# RNG_Board.net
KiCad netlist of a schematic drawn in EAGLE
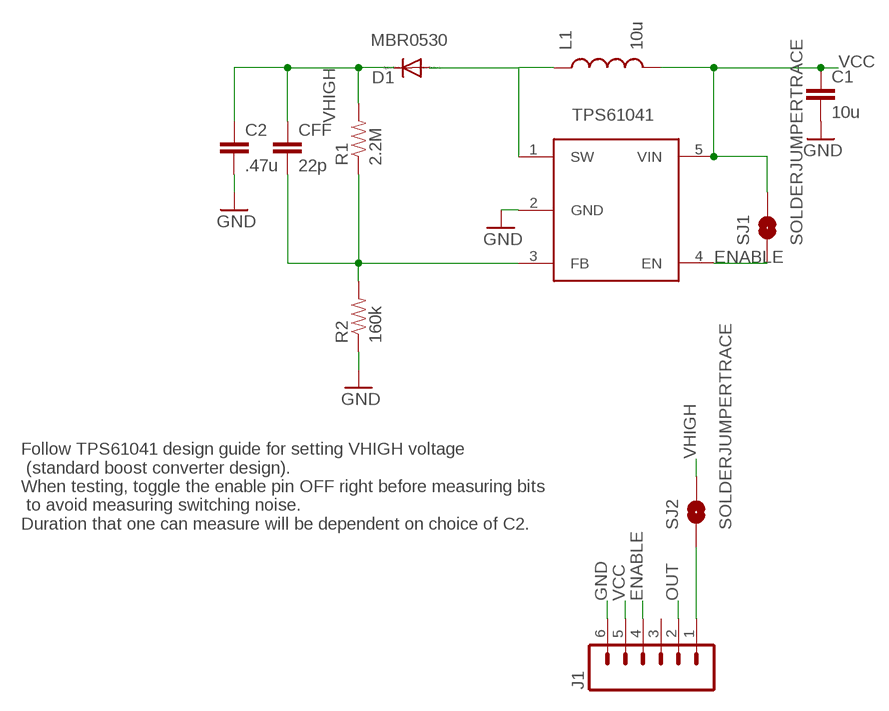
[diagram p0: schematic, sheet 1]
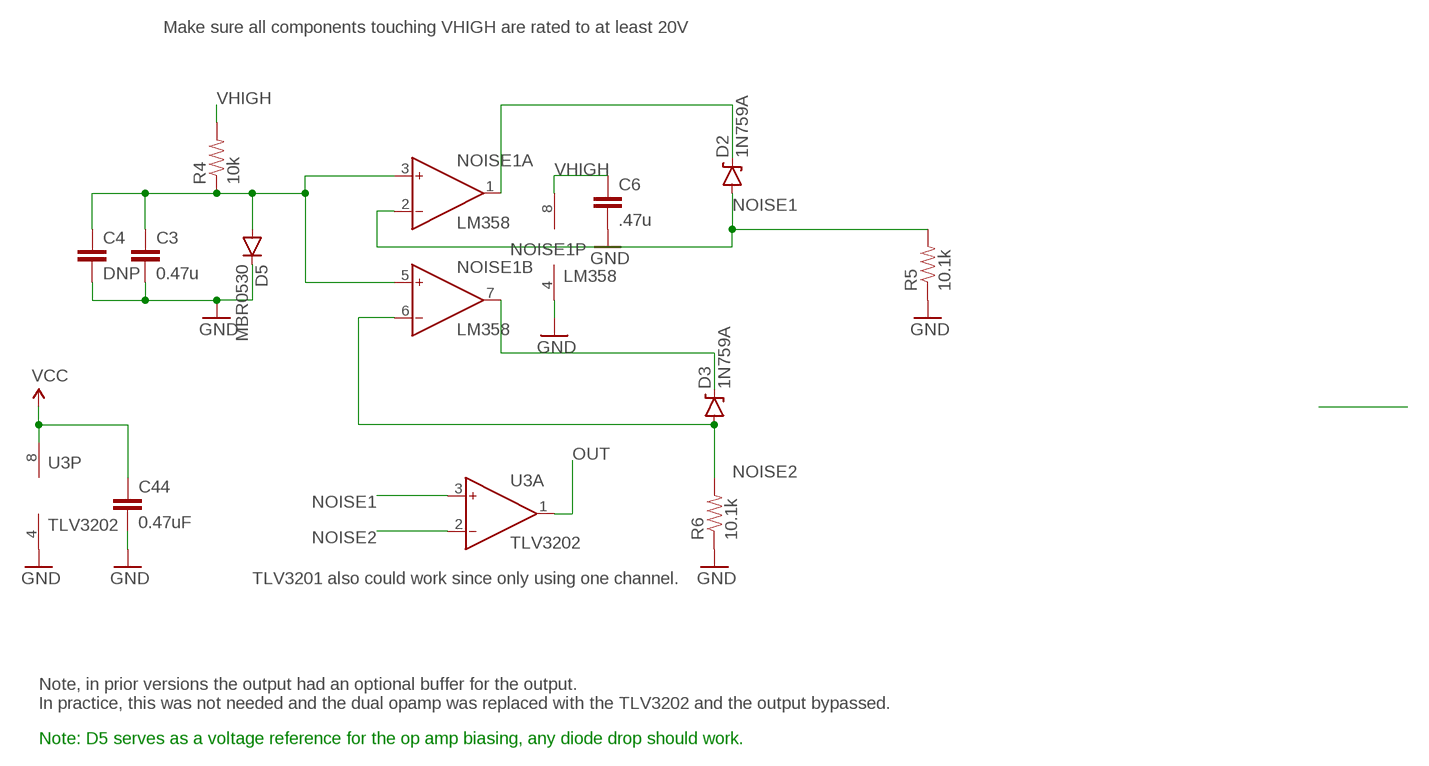
[diagram p1: schematic, sheet 2]

(export (version "E")
  (design (tool "Eeschema 10.0.6"))
  (components
    (comp (ref "C1")
      (value "10u")
      (footprint "eagle-import:0603-CAP")
      (libsource (lib "eagle-import") (part "CAP0603-CAP"))
    )
    (comp (ref "C2")
      (value ".47u")
      (footprint "eagle-import:0603-CAP")
      (libsource (lib "eagle-import") (part "CAP0603-CAP"))
    )
    (comp (ref "CFF")
      (value "22p")
      (footprint "eagle-import:0603-CAP")
      (libsource (lib "eagle-import") (part "CAP0603-CAP"))
    )
    (comp (ref "D1")
      (value "MBR0530")
      (footprint "eagle-import:SOD-123_MINI-SMA")
      (libsource (lib "eagle-import") (part "CGRM400-G1"))
    )
    (comp (ref "J1")
      (value "M06SILK_FEMALE_PTH")
      (footprint "eagle-import:1X06")
      (libsource (lib "eagle-import") (part "M06SILK_FEMALE_PTH"))
    )
    (comp (ref "L1")
      (value "10u")
      (footprint "eagle-import:0805")
      (libsource (lib "eagle-import") (part "INDUCTOR0805"))
    )
    (comp (ref "R1")
      (value "2.2M")
      (footprint "eagle-import:0603-RES")
      (libsource (lib "eagle-import") (part "0.27OHM-1/10W-1%(0603)"))
    )
    (comp (ref "R2")
      (value "160k")
      (footprint "eagle-import:0603-RES")
      (libsource (lib "eagle-import") (part "0.27OHM-1/10W-1%(0603)"))
    )
    (comp (ref "SJ1")
      (value "SOLDERJUMPERTRACE")
      (footprint "eagle-import:SJ_2S-TRACE")
      (libsource (lib "eagle-import") (part "SOLDERJUMPERTRACE"))
    )
    (comp (ref "SJ2")
      (value "SOLDERJUMPERTRACE")
      (footprint "eagle-import:SJ_2S-TRACE")
      (libsource (lib "eagle-import") (part "SOLDERJUMPERTRACE"))
    )
    (comp (ref "U$1")
      (value "TPS61040")
      (footprint "eagle-import:SOT23-5")
      (libsource (lib "eagle-import") (part "TPS61040"))
    )
    (comp (ref "C3")
      (value "0.47u")
      (footprint "eagle-import:0603-CAP")
      (libsource (lib "eagle-import") (part "SparkFun-Passives_CAP0603-CAP"))
    )
    (comp (ref "C4")
      (value "DNP")
      (footprint "eagle-import:0603-CAP")
      (libsource (lib "eagle-import") (part "SparkFun-Passives_CAP0603-CAP"))
    )
    (comp (ref "C6")
      (value ".47u")
      (footprint "eagle-import:0603-CAP")
      (libsource (lib "eagle-import") (part "CAP0603-CAP"))
    )
    (comp (ref "C44")
      (value "0.47uF")
      (footprint "eagle-import:C0603")
      (libsource (lib "eagle-import") (part "C-EUC0603"))
    )
    (comp (ref "D2")
      (value "1N759A")
      (footprint "eagle-import:DIODE-ZENER")
      (fields (field (name "MPN") "610-1N759A"))
      (libsource (lib "eagle-import") (part "DIODE-ZENERPTH"))
    )
    (comp (ref "D3")
      (value "1N759A")
      (footprint "eagle-import:DIODE-ZENER")
      (fields (field (name "MPN") "610-1N759A"))
      (libsource (lib "eagle-import") (part "DIODE-ZENERPTH"))
    )
    (comp (ref "D5")
      (value "MBR0530")
      (footprint "eagle-import:SOD-123")
      (libsource (lib "eagle-import") (part "DIODESOD123"))
    )
    (comp (ref "NOISE1")
      (value "LM358")
      (footprint "eagle-import:SO8")
      (fields (field (name "MF") "ALTERA CORPORATION") (field (name "MPN") "AD712KRZ"))
      (libsource (lib "eagle-import") (part "AD712R"))
    )
    (comp (ref "R4")
      (value "10k")
      (footprint "eagle-import:0603-RES")
      (libsource (lib "eagle-import") (part "RESISTOR0603"))
    )
    (comp (ref "R5")
      (value "10.1k")
      (footprint "eagle-import:0603-RES")
      (libsource (lib "eagle-import") (part "RESISTOR0603"))
    )
    (comp (ref "R6")
      (value "10.1k")
      (footprint "eagle-import:0603-RES")
      (libsource (lib "eagle-import") (part "RESISTOR0603"))
    )
    (comp (ref "U3")
      (value "TLV3202")
      (footprint "eagle-import:SO8")
      (fields
        (field (name "MF") "ALTERA CORPORATION")
        (field (name "MPN") "AD712KRZ")
        (field (name "DKPN") "296-34773-1-ND")
      )
      (libsource (lib "eagle-import") (part "imix_AD712R"))
    )
  )
  (nets
    (net (code "1") (name "ENABLE") (class "Default")
      (node (ref "J1") (pin "4") (pinfunction "4_4") (pintype "passive"))
      (node (ref "SJ1") (pin "1") (pinfunction "1_1") (pintype "passive"))
      (node (ref "U$1") (pin "4") (pinfunction "EN_4") (pintype "bidirectional"))
    )
    (net (code "2") (name "GND") (class "Default")
      (node (ref "C1") (pin "2") (pinfunction "2_2") (pintype "passive"))
      (node (ref "C2") (pin "2") (pinfunction "2_2") (pintype "passive"))
      (node (ref "C3") (pin "2") (pinfunction "2_2") (pintype "passive"))
      (node (ref "C4") (pin "2") (pinfunction "2_2") (pintype "passive"))
      (node (ref "C44") (pin "2") (pinfunction "2_2") (pintype "passive"))
      (node (ref "C6") (pin "2") (pinfunction "2_2") (pintype "passive"))
      (node (ref "D5") (pin "C") (pinfunction "C_C") (pintype "passive"))
      (node (ref "J1") (pin "6") (pinfunction "6_6") (pintype "passive"))
      (node (ref "NOISE1") (pin "4") (pinfunction "V-_4") (pintype "power_in"))
      (node (ref "R2") (pin "1") (pinfunction "1_1") (pintype "passive"))
      (node (ref "R5") (pin "1") (pinfunction "1_1") (pintype "passive"))
      (node (ref "R6") (pin "1") (pinfunction "1_1") (pintype "passive"))
      (node (ref "U$1") (pin "2") (pinfunction "GND_2") (pintype "bidirectional"))
      (node (ref "U3") (pin "4") (pinfunction "V-_4") (pintype "power_in"))
    )
    (net (code "3") (name "NOISE1") (class "Default")
      (node (ref "D2") (pin "P$2") (pinfunction "A_P$2") (pintype "passive"))
      (node (ref "NOISE1") (pin "2") (pinfunction "IN-_2") (pintype "input"))
      (node (ref "R5") (pin "2") (pinfunction "2_2") (pintype "passive"))
      (node (ref "U3") (pin "3") (pinfunction "IN+_3") (pintype "input"))
    )
    (net (code "4") (name "NOISE2") (class "Default")
      (node (ref "D3") (pin "P$2") (pinfunction "A_P$2") (pintype "passive"))
      (node (ref "NOISE1") (pin "6") (pinfunction "IN-_6") (pintype "input"))
      (node (ref "R6") (pin "2") (pinfunction "2_2") (pintype "passive"))
      (node (ref "U3") (pin "2") (pinfunction "IN-_2") (pintype "input"))
    )
    (net (code "5") (name "Net-(D2-C)") (class "Default")
      (node (ref "D2") (pin "P$1") (pinfunction "C_P$1") (pintype "passive"))
      (node (ref "NOISE1") (pin "1") (pinfunction "OUT_1") (pintype "output"))
    )
    (net (code "6") (name "Net-(D3-C)") (class "Default")
      (node (ref "D3") (pin "P$1") (pinfunction "C_P$1") (pintype "passive"))
      (node (ref "NOISE1") (pin "7") (pinfunction "OUT_7") (pintype "output"))
    )
    (net (code "7") (name "Net-(J1-Pad1)") (class "Default")
      (node (ref "J1") (pin "1") (pinfunction "1_1") (pintype "passive"))
      (node (ref "SJ2") (pin "1") (pinfunction "1_1") (pintype "passive"))
    )
    (net (code "8") (name "Net-(NOISE1A-IN+)") (class "Default")
      (node (ref "C3") (pin "1") (pinfunction "1_1") (pintype "passive"))
      (node (ref "C4") (pin "1") (pinfunction "1_1") (pintype "passive"))
      (node (ref "D5") (pin "A") (pinfunction "A_A") (pintype "passive"))
      (node (ref "NOISE1") (pin "3") (pinfunction "IN+_3") (pintype "input"))
      (node (ref "NOISE1") (pin "5") (pinfunction "IN+_5") (pintype "input"))
      (node (ref "R4") (pin "1") (pinfunction "1_1") (pintype "passive"))
    )
    (net (code "9") (name "Net-(U$1-FB)") (class "Default")
      (node (ref "CFF") (pin "2") (pinfunction "2_2") (pintype "passive"))
      (node (ref "R1") (pin "1") (pinfunction "1_1") (pintype "passive"))
      (node (ref "R2") (pin "2") (pinfunction "2_2") (pintype "passive"))
      (node (ref "U$1") (pin "3") (pinfunction "FB_3") (pintype "bidirectional"))
    )
    (net (code "10") (name "Net-(U$1-SW)") (class "Default")
      (node (ref "D1") (pin "A") (pinfunction "A_A") (pintype "passive"))
      (node (ref "L1") (pin "1") (pinfunction "1_1") (pintype "passive"))
      (node (ref "U$1") (pin "1") (pinfunction "SW_1") (pintype "bidirectional"))
    )
    (net (code "11") (name "OUT") (class "Default")
      (node (ref "J1") (pin "2") (pinfunction "2_2") (pintype "passive"))
      (node (ref "U3") (pin "1") (pinfunction "OUT_1") (pintype "output"))
    )
    (net (code "12") (name "VCC") (class "Default")
      (node (ref "C1") (pin "1") (pinfunction "1_1") (pintype "passive"))
      (node (ref "C44") (pin "1") (pinfunction "1_1") (pintype "passive"))
      (node (ref "J1") (pin "5") (pinfunction "5_5") (pintype "passive"))
      (node (ref "L1") (pin "2") (pinfunction "2_2") (pintype "passive"))
      (node (ref "SJ1") (pin "2") (pinfunction "2_2") (pintype "passive"))
      (node (ref "U$1") (pin "5") (pinfunction "VIN_5") (pintype "bidirectional"))
      (node (ref "U3") (pin "8") (pinfunction "V+_8") (pintype "power_in"))
    )
    (net (code "13") (name "VHIGH") (class "Default")
      (node (ref "C2") (pin "1") (pinfunction "1_1") (pintype "passive"))
      (node (ref "C6") (pin "1") (pinfunction "1_1") (pintype "passive"))
      (node (ref "CFF") (pin "1") (pinfunction "1_1") (pintype "passive"))
      (node (ref "D1") (pin "C") (pinfunction "C_C") (pintype "passive"))
      (node (ref "NOISE1") (pin "8") (pinfunction "V+_8") (pintype "power_in"))
      (node (ref "R1") (pin "2") (pinfunction "2_2") (pintype "passive"))
      (node (ref "R4") (pin "2") (pinfunction "2_2") (pintype "passive"))
      (node (ref "SJ2") (pin "2") (pinfunction "2_2") (pintype "passive"))
    )
    (net (code "14") (name "unconnected-(J1-Pad3)") (class "Default")
      (node (ref "J1") (pin "3") (pinfunction "3_3") (pintype "passive"))
    )
  )
)
